# sclift_esp.net
KiCad netlist of a schematic drawn in EAGLE
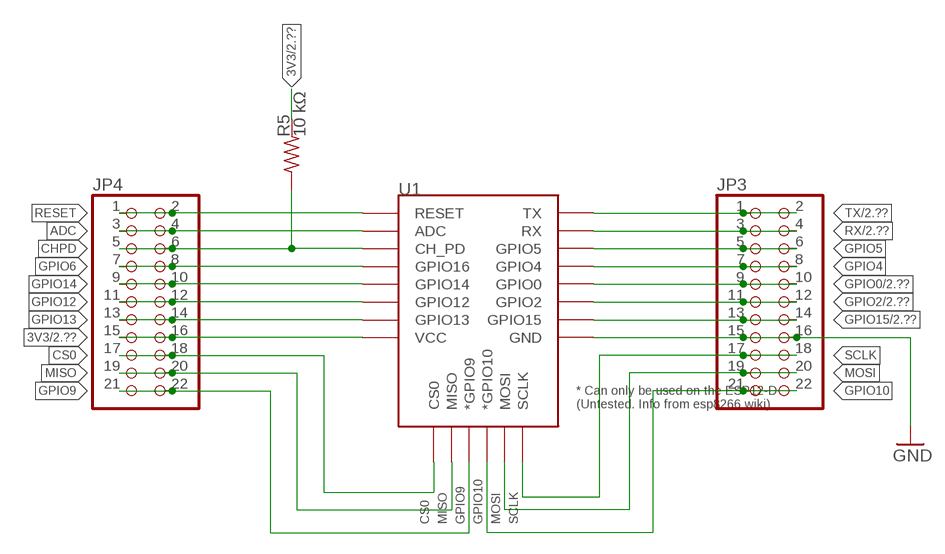
[diagram p0: schematic, sheet 1]
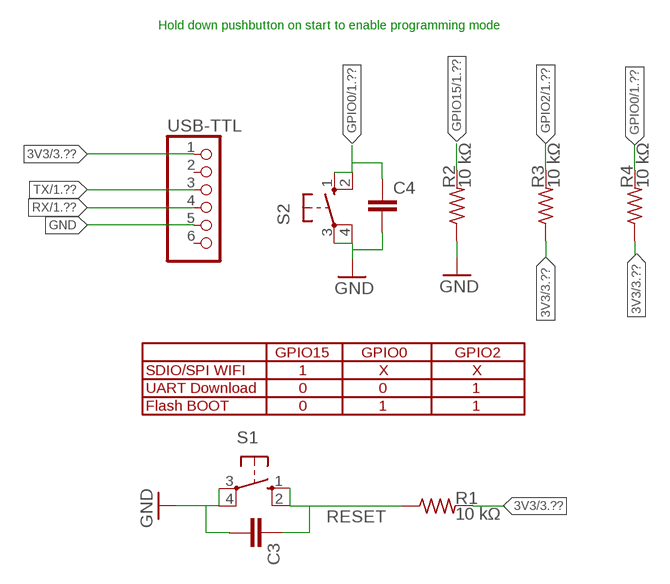
[diagram p1: schematic, sheet 2]
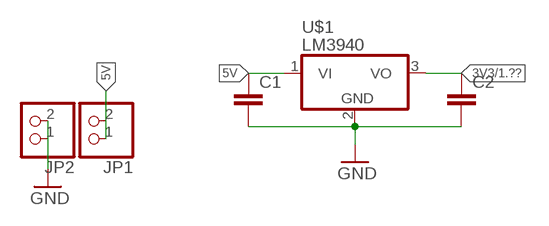
[diagram p2: schematic, sheet 3]

(export (version "E")
  (design (tool "Eeschema 10.0.6"))
  (components
    (comp (ref "C1")
      (value "C-EU025-024X044")
      (footprint "eagle-import:C025-024X044")
      (libsource (lib "eagle-import") (part "C-EU025-024X044"))
    )
    (comp (ref "C2")
      (value "C-EU025-024X044")
      (footprint "eagle-import:C025-024X044")
      (libsource (lib "eagle-import") (part "C-EU025-024X044"))
    )
    (comp (ref "JP1")
      (value "PINHD-1X2")
      (footprint "eagle-import:1X02")
      (libsource (lib "eagle-import") (part "PINHD-1X2"))
    )
    (comp (ref "JP2")
      (value "PINHD-1X2")
      (footprint "eagle-import:1X02")
      (libsource (lib "eagle-import") (part "PINHD-1X2"))
    )
    (comp (ref "U$1")
      (value "LM3940")
      (footprint "eagle-import:TO220H")
      (libsource (lib "eagle-import") (part "LM3940"))
    )
    (comp (ref "JP3")
      (value "PINHD-2X11")
      (footprint "eagle-import:2X11")
      (libsource (lib "eagle-import") (part "PINHD-2X11"))
    )
    (comp (ref "JP4")
      (value "PINHD-2X11")
      (footprint "eagle-import:2X11")
      (libsource (lib "eagle-import") (part "PINHD-2X11"))
    )
    (comp (ref "R5")
      (value "10 kΩ")
      (footprint "eagle-import:0204_7")
      (libsource (lib "eagle-import") (part "R-US_0204/7"))
    )
    (comp (ref "U1")
      (value "ESP12ESMD")
      (footprint "eagle-import:ESP12E-SMD")
      (libsource (lib "eagle-import") (part "ESP12ESMD"))
    )
    (comp (ref "C3")
      (value "C-EU025-024X044")
      (footprint "eagle-import:C025-024X044")
      (libsource (lib "eagle-import") (part "C-EU025-024X044"))
    )
    (comp (ref "C4")
      (value "C-EU025-024X044")
      (footprint "eagle-import:C025-024X044")
      (libsource (lib "eagle-import") (part "C-EU025-024X044"))
    )
    (comp (ref "R1")
      (value "10 kΩ")
      (footprint "eagle-import:0204_7")
      (libsource (lib "eagle-import") (part "R-US_0204/7"))
    )
    (comp (ref "R2")
      (value "10 kΩ")
      (footprint "eagle-import:0204_7")
      (libsource (lib "eagle-import") (part "R-US_0204/7"))
    )
    (comp (ref "R3")
      (value "10 kΩ")
      (footprint "eagle-import:0204_7")
      (libsource (lib "eagle-import") (part "R-US_0204/7"))
    )
    (comp (ref "R4")
      (value "10 kΩ")
      (footprint "eagle-import:0204_7")
      (libsource (lib "eagle-import") (part "R-US_0204/7"))
    )
    (comp (ref "S1")
      (value "10-XX")
      (footprint "eagle-import:B3F-10XX")
      (fields (field (name "MPN") "B3F-1000"))
      (libsource (lib "eagle-import") (part "10-XX"))
    )
    (comp (ref "S2")
      (value "10-XX")
      (footprint "eagle-import:B3F-10XX")
      (fields (field (name "MPN") "B3F-1000"))
      (libsource (lib "eagle-import") (part "10-XX"))
    )
    (comp (ref "USB-TTL")
      (value "PINHD-1X6")
      (footprint "eagle-import:1X06")
      (libsource (lib "eagle-import") (part "PINHD-1X6"))
    )
  )
  (nets
    (net (code "1") (name "3V3") (class "Default")
      (node (ref "C2") (pin "1") (pinfunction "1_1") (pintype "passive"))
      (node (ref "JP4") (pin "15") (pinfunction "15_15") (pintype "passive"))
      (node (ref "JP4") (pin "16") (pinfunction "16_16") (pintype "passive"))
      (node (ref "R1") (pin "2") (pinfunction "2_2") (pintype "passive"))
      (node (ref "R3") (pin "1") (pinfunction "1_1") (pintype "passive"))
      (node (ref "R4") (pin "1") (pinfunction "1_1") (pintype "passive"))
      (node (ref "R5") (pin "2") (pinfunction "2_2") (pintype "passive"))
      (node (ref "U$1") (pin "3") (pinfunction "VO_3") (pintype "passive"))
      (node (ref "U1") (pin "VCC") (pinfunction "VCC_VCC") (pintype "bidirectional"))
      (node (ref "USB-TTL") (pin "1") (pinfunction "1_1") (pintype "passive"))
    )
    (net (code "2") (name "5V") (class "Default")
      (node (ref "C1") (pin "1") (pinfunction "1_1") (pintype "passive"))
      (node (ref "JP1") (pin "1") (pinfunction "1_1") (pintype "passive"))
      (node (ref "JP1") (pin "2") (pinfunction "2_2") (pintype "passive"))
      (node (ref "U$1") (pin "1") (pinfunction "VI_1") (pintype "input"))
    )
    (net (code "3") (name "ADC") (class "Default")
      (node (ref "JP4") (pin "3") (pinfunction "3_3") (pintype "passive"))
      (node (ref "JP4") (pin "4") (pinfunction "4_4") (pintype "passive"))
      (node (ref "U1") (pin "ADC") (pinfunction "ADC_ADC") (pintype "bidirectional"))
    )
    (net (code "4") (name "CHPD") (class "Default")
      (node (ref "JP4") (pin "5") (pinfunction "5_5") (pintype "passive"))
      (node (ref "JP4") (pin "6") (pinfunction "6_6") (pintype "passive"))
      (node (ref "R5") (pin "1") (pinfunction "1_1") (pintype "passive"))
      (node (ref "U1") (pin "CH_PD") (pinfunction "CH_PD_CH_PD") (pintype "bidirectional"))
    )
    (net (code "5") (name "CS0") (class "Default")
      (node (ref "JP4") (pin "17") (pinfunction "17_17") (pintype "passive"))
      (node (ref "JP4") (pin "18") (pinfunction "18_18") (pintype "passive"))
      (node (ref "U1") (pin "CS0") (pinfunction "CS0_CS0") (pintype "bidirectional"))
    )
    (net (code "6") (name "GND") (class "Default")
      (node (ref "C1") (pin "2") (pinfunction "2_2") (pintype "passive"))
      (node (ref "C2") (pin "2") (pinfunction "2_2") (pintype "passive"))
      (node (ref "C3") (pin "2") (pinfunction "2_2") (pintype "passive"))
      (node (ref "C4") (pin "2") (pinfunction "2_2") (pintype "passive"))
      (node (ref "JP2") (pin "1") (pinfunction "1_1") (pintype "passive"))
      (node (ref "JP2") (pin "2") (pinfunction "2_2") (pintype "passive"))
      (node (ref "JP3") (pin "15") (pinfunction "15_15") (pintype "passive"))
      (node (ref "JP3") (pin "16") (pinfunction "16_16") (pintype "passive"))
      (node (ref "R2") (pin "1") (pinfunction "1_1") (pintype "passive"))
      (node (ref "S1") (pin "3") (pinfunction "P_3") (pintype "passive"))
      (node (ref "S1") (pin "4") (pinfunction "P1_4") (pintype "passive"))
      (node (ref "S2") (pin "3") (pinfunction "P_3") (pintype "passive"))
      (node (ref "S2") (pin "4") (pinfunction "P1_4") (pintype "passive"))
      (node (ref "U$1") (pin "2") (pinfunction "GND_2") (pintype "passive"))
      (node (ref "U1") (pin "GND") (pinfunction "GND_GND") (pintype "bidirectional"))
      (node (ref "USB-TTL") (pin "5") (pinfunction "5_5") (pintype "passive"))
    )
    (net (code "7") (name "GPIO0") (class "Default")
      (node (ref "C4") (pin "1") (pinfunction "1_1") (pintype "passive"))
      (node (ref "JP3") (pin "10") (pinfunction "10_10") (pintype "passive"))
      (node (ref "JP3") (pin "9") (pinfunction "9_9") (pintype "passive"))
      (node (ref "R4") (pin "2") (pinfunction "2_2") (pintype "passive"))
      (node (ref "S2") (pin "1") (pinfunction "S_1") (pintype "passive"))
      (node (ref "S2") (pin "2") (pinfunction "S1_2") (pintype "passive"))
      (node (ref "U1") (pin "GPIO0") (pinfunction "GPIO0_GPIO0") (pintype "bidirectional"))
    )
    (net (code "8") (name "GPIO2") (class "Default")
      (node (ref "JP3") (pin "11") (pinfunction "11_11") (pintype "passive"))
      (node (ref "JP3") (pin "12") (pinfunction "12_12") (pintype "passive"))
      (node (ref "R3") (pin "2") (pinfunction "2_2") (pintype "passive"))
      (node (ref "U1") (pin "GPIO2") (pinfunction "GPIO2_GPIO2") (pintype "bidirectional"))
    )
    (net (code "9") (name "GPIO4") (class "Default")
      (node (ref "JP3") (pin "7") (pinfunction "7_7") (pintype "passive"))
      (node (ref "JP3") (pin "8") (pinfunction "8_8") (pintype "passive"))
      (node (ref "U1") (pin "GPIO4") (pinfunction "GPIO4_GPIO4") (pintype "bidirectional"))
    )
    (net (code "10") (name "GPIO5") (class "Default")
      (node (ref "JP3") (pin "5") (pinfunction "5_5") (pintype "passive"))
      (node (ref "JP3") (pin "6") (pinfunction "6_6") (pintype "passive"))
      (node (ref "U1") (pin "GPIO5") (pinfunction "GPIO5_GPIO5") (pintype "bidirectional"))
    )
    (net (code "11") (name "GPIO6") (class "Default")
      (node (ref "JP4") (pin "7") (pinfunction "7_7") (pintype "passive"))
      (node (ref "JP4") (pin "8") (pinfunction "8_8") (pintype "passive"))
      (node (ref "U1") (pin "GPIO16") (pinfunction "GPIO16_GPIO16") (pintype "bidirectional"))
    )
    (net (code "12") (name "GPIO9") (class "Default")
      (node (ref "JP4") (pin "21") (pinfunction "21_21") (pintype "passive"))
      (node (ref "JP4") (pin "22") (pinfunction "22_22") (pintype "passive"))
      (node (ref "U1") (pin "GPIO9") (pinfunction "*GPIO9_GPIO9") (pintype "bidirectional"))
    )
    (net (code "13") (name "GPIO10") (class "Default")
      (node (ref "JP3") (pin "21") (pinfunction "21_21") (pintype "passive"))
      (node (ref "JP3") (pin "22") (pinfunction "22_22") (pintype "passive"))
      (node (ref "U1") (pin "GPIO10") (pinfunction "*GPIO10_GPIO10") (pintype "bidirectional"))
    )
    (net (code "14") (name "GPIO12") (class "Default")
      (node (ref "JP4") (pin "11") (pinfunction "11_11") (pintype "passive"))
      (node (ref "JP4") (pin "12") (pinfunction "12_12") (pintype "passive"))
      (node (ref "U1") (pin "GPIO12") (pinfunction "GPIO12_GPIO12") (pintype "bidirectional"))
    )
    (net (code "15") (name "GPIO13") (class "Default")
      (node (ref "JP4") (pin "13") (pinfunction "13_13") (pintype "passive"))
      (node (ref "JP4") (pin "14") (pinfunction "14_14") (pintype "passive"))
      (node (ref "U1") (pin "GPIO13") (pinfunction "GPIO13_GPIO13") (pintype "bidirectional"))
    )
    (net (code "16") (name "GPIO14") (class "Default")
      (node (ref "JP4") (pin "10") (pinfunction "10_10") (pintype "passive"))
      (node (ref "JP4") (pin "9") (pinfunction "9_9") (pintype "passive"))
      (node (ref "U1") (pin "GPIO14") (pinfunction "GPIO14_GPIO14") (pintype "bidirectional"))
    )
    (net (code "17") (name "GPIO15") (class "Default")
      (node (ref "JP3") (pin "13") (pinfunction "13_13") (pintype "passive"))
      (node (ref "JP3") (pin "14") (pinfunction "14_14") (pintype "passive"))
      (node (ref "R2") (pin "2") (pinfunction "2_2") (pintype "passive"))
      (node (ref "U1") (pin "GPIO15") (pinfunction "GPIO15_GPIO15") (pintype "bidirectional"))
    )
    (net (code "18") (name "MISO") (class "Default")
      (node (ref "JP4") (pin "19") (pinfunction "19_19") (pintype "passive"))
      (node (ref "JP4") (pin "20") (pinfunction "20_20") (pintype "passive"))
      (node (ref "U1") (pin "MISO") (pinfunction "MISO_MISO") (pintype "bidirectional"))
    )
    (net (code "19") (name "MOSI") (class "Default")
      (node (ref "JP3") (pin "19") (pinfunction "19_19") (pintype "passive"))
      (node (ref "JP3") (pin "20") (pinfunction "20_20") (pintype "passive"))
      (node (ref "U1") (pin "MOSI") (pinfunction "MOSI_MOSI") (pintype "bidirectional"))
    )
    (net (code "20") (name "RESET") (class "Default")
      (node (ref "C3") (pin "1") (pinfunction "1_1") (pintype "passive"))
      (node (ref "JP4") (pin "1") (pinfunction "1_1") (pintype "passive"))
      (node (ref "JP4") (pin "2") (pinfunction "2_2") (pintype "passive"))
      (node (ref "R1") (pin "1") (pinfunction "1_1") (pintype "passive"))
      (node (ref "S1") (pin "1") (pinfunction "S_1") (pintype "passive"))
      (node (ref "S1") (pin "2") (pinfunction "S1_2") (pintype "passive"))
      (node (ref "U1") (pin "RESET") (pinfunction "RESET_RESET") (pintype "bidirectional"))
    )
    (net (code "21") (name "RX") (class "Default")
      (node (ref "JP3") (pin "3") (pinfunction "3_3") (pintype "passive"))
      (node (ref "JP3") (pin "4") (pinfunction "4_4") (pintype "passive"))
      (node (ref "U1") (pin "RXD0") (pinfunction "RX_RXD0") (pintype "bidirectional"))
      (node (ref "USB-TTL") (pin "4") (pinfunction "4_4") (pintype "passive"))
    )
    (net (code "22") (name "SCLK") (class "Default")
      (node (ref "JP3") (pin "17") (pinfunction "17_17") (pintype "passive"))
      (node (ref "JP3") (pin "18") (pinfunction "18_18") (pintype "passive"))
      (node (ref "U1") (pin "SCLK") (pinfunction "SCLK_SCLK") (pintype "bidirectional"))
    )
    (net (code "23") (name "TX") (class "Default")
      (node (ref "JP3") (pin "1") (pinfunction "1_1") (pintype "passive"))
      (node (ref "JP3") (pin "2") (pinfunction "2_2") (pintype "passive"))
      (node (ref "U1") (pin "TXD0") (pinfunction "TX_TXD0") (pintype "bidirectional"))
      (node (ref "USB-TTL") (pin "3") (pinfunction "3_3") (pintype "passive"))
    )
    (net (code "24") (name "unconnected-(USB-TTL-Pad2)") (class "Default")
      (node (ref "USB-TTL") (pin "2") (pinfunction "2_2") (pintype "passive"))
    )
    (net (code "25") (name "unconnected-(USB-TTL-Pad6)") (class "Default")
      (node (ref "USB-TTL") (pin "6") (pinfunction "6_6") (pintype "passive"))
    )
  )
)
